# backplane-manual_selection.net
KiCad netlist of a schematic drawn in EAGLE
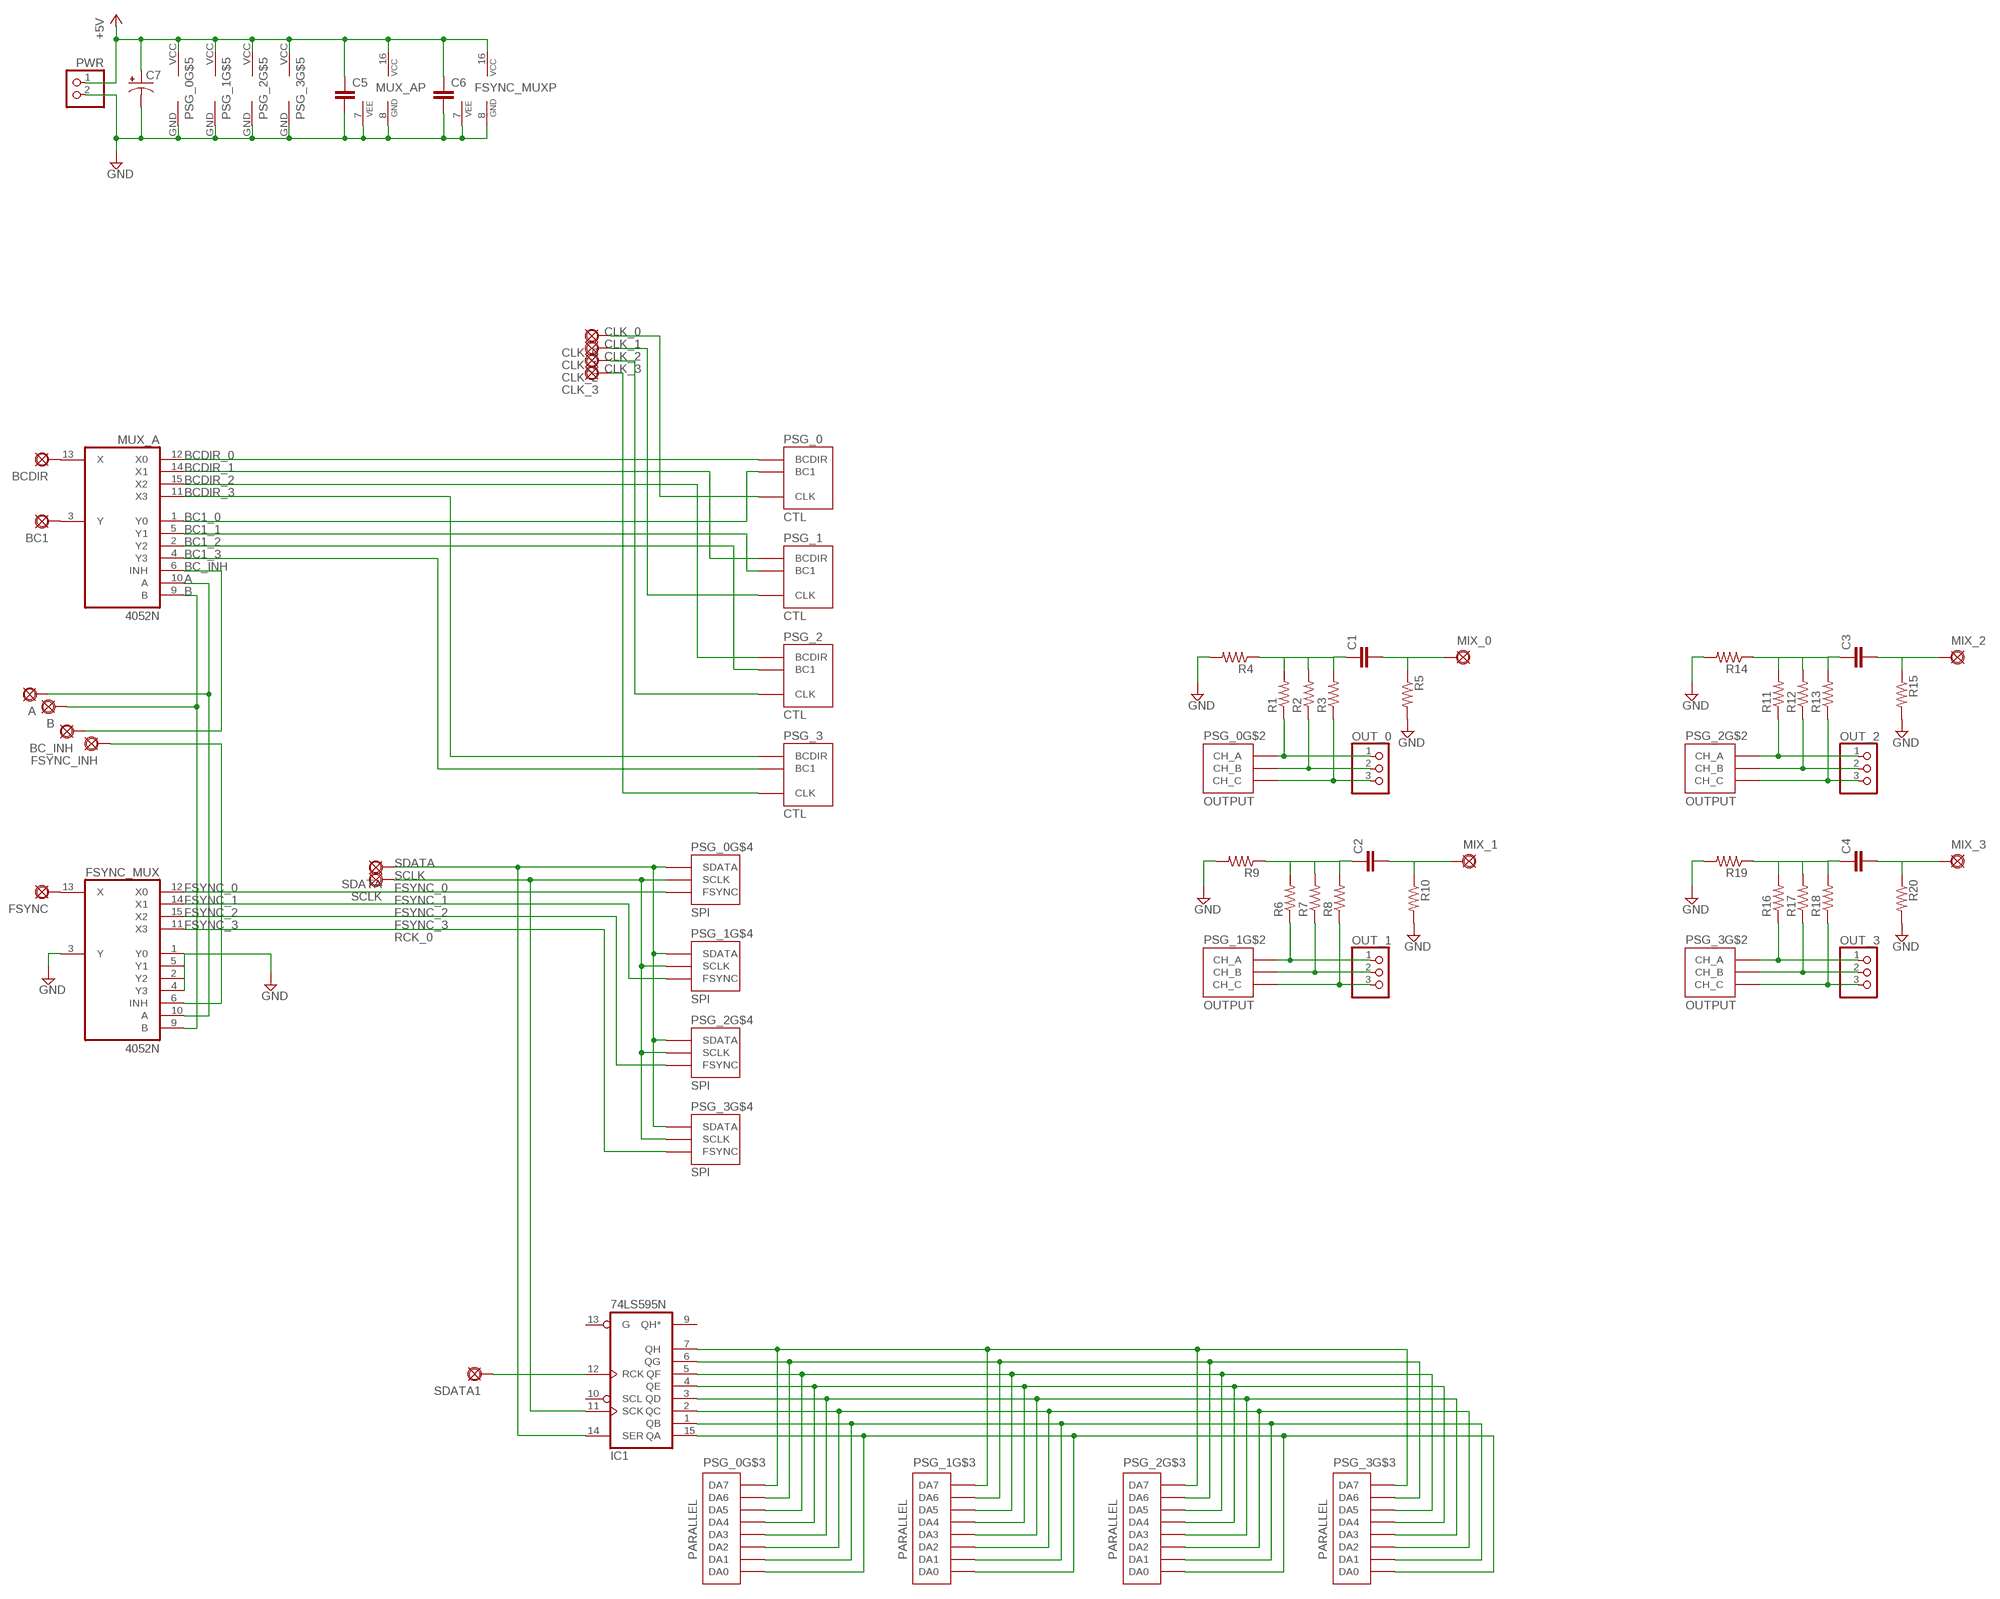
[diagram p0: schematic, sheet 1]

(export (version "E")
  (design (tool "Eeschema 10.0.6"))
  (components
    (comp (ref "A")
      (value "PAD")
      (footprint "eagle-import:SQUARE")
      (libsource (lib "eagle-import") (part "PAD"))
    )
    (comp (ref "B")
      (value "PAD")
      (footprint "eagle-import:SQUARE")
      (libsource (lib "eagle-import") (part "PAD"))
    )
    (comp (ref "BC1")
      (value "PAD")
      (footprint "eagle-import:SQUARE")
      (libsource (lib "eagle-import") (part "PAD"))
    )
    (comp (ref "BCDIR")
      (value "PAD")
      (footprint "eagle-import:SQUARE")
      (libsource (lib "eagle-import") (part "PAD"))
    )
    (comp (ref "BC_INH")
      (value "PAD")
      (footprint "eagle-import:SQUARE")
      (libsource (lib "eagle-import") (part "PAD"))
    )
    (comp (ref "C1")
      (value "080X0452")
      (footprint "eagle-import:080X045")
      (libsource (lib "eagle-import") (part "080X0452"))
    )
    (comp (ref "C2")
      (value "080X0452")
      (footprint "eagle-import:080X045")
      (libsource (lib "eagle-import") (part "080X0452"))
    )
    (comp (ref "C3")
      (value "080X0452")
      (footprint "eagle-import:080X045")
      (libsource (lib "eagle-import") (part "080X0452"))
    )
    (comp (ref "C4")
      (value "080X0452")
      (footprint "eagle-import:080X045")
      (libsource (lib "eagle-import") (part "080X0452"))
    )
    (comp (ref "C5")
      (value "050X030_0251")
      (footprint "eagle-import:050X030_025")
      (libsource (lib "eagle-import") (part "050X030_0251"))
    )
    (comp (ref "C6")
      (value "050X030_0251")
      (footprint "eagle-import:050X030_025")
      (libsource (lib "eagle-import") (part "050X030_0251"))
    )
    (comp (ref "C7")
      (value "0631")
      (footprint "eagle-import:063_025")
      (libsource (lib "eagle-import") (part "0631"))
    )
    (comp (ref "CLK_0")
      (value "PAD")
      (footprint "eagle-import:SQUARE")
      (libsource (lib "eagle-import") (part "PAD"))
    )
    (comp (ref "CLK_1")
      (value "PAD")
      (footprint "eagle-import:SQUARE")
      (libsource (lib "eagle-import") (part "PAD"))
    )
    (comp (ref "CLK_2")
      (value "PAD")
      (footprint "eagle-import:SQUARE")
      (libsource (lib "eagle-import") (part "PAD"))
    )
    (comp (ref "CLK_3")
      (value "PAD")
      (footprint "eagle-import:SQUARE")
      (libsource (lib "eagle-import") (part "PAD"))
    )
    (comp (ref "FSYNC")
      (value "PAD")
      (footprint "eagle-import:SQUARE")
      (libsource (lib "eagle-import") (part "PAD"))
    )
    (comp (ref "FSYNC_INH")
      (value "PAD")
      (footprint "eagle-import:SQUARE")
      (libsource (lib "eagle-import") (part "PAD"))
    )
    (comp (ref "FSYNC_MUX")
      (value "4052N")
      (footprint "eagle-import:DIL16")
      (libsource (lib "eagle-import") (part "4052N"))
    )
    (comp (ref "IC1")
      (value "74LS595N")
      (footprint "eagle-import:DIL16")
      (libsource (lib "eagle-import") (part "74595NLS"))
    )
    (comp (ref "MIX_0")
      (value "PAD")
      (footprint "eagle-import:SQUARE")
      (libsource (lib "eagle-import") (part "PAD"))
    )
    (comp (ref "MIX_1")
      (value "PAD")
      (footprint "eagle-import:SQUARE")
      (libsource (lib "eagle-import") (part "PAD"))
    )
    (comp (ref "MIX_2")
      (value "PAD")
      (footprint "eagle-import:SQUARE")
      (libsource (lib "eagle-import") (part "PAD"))
    )
    (comp (ref "MIX_3")
      (value "PAD")
      (footprint "eagle-import:SQUARE")
      (libsource (lib "eagle-import") (part "PAD"))
    )
    (comp (ref "MUX_A")
      (value "4052N")
      (footprint "eagle-import:DIL16")
      (libsource (lib "eagle-import") (part "4052N"))
    )
    (comp (ref "OUT_0")
      (value "PINHD-1X3")
      (footprint "eagle-import:1X03")
      (libsource (lib "eagle-import") (part "PINHD-1X3"))
    )
    (comp (ref "OUT_1")
      (value "PINHD-1X3")
      (footprint "eagle-import:1X03")
      (libsource (lib "eagle-import") (part "PINHD-1X3"))
    )
    (comp (ref "OUT_2")
      (value "PINHD-1X3")
      (footprint "eagle-import:1X03")
      (libsource (lib "eagle-import") (part "PINHD-1X3"))
    )
    (comp (ref "OUT_3")
      (value "PINHD-1X3")
      (footprint "eagle-import:1X03")
      (libsource (lib "eagle-import") (part "PINHD-1X3"))
    )
    (comp (ref "PSG_0")
      (value "PSG_DAUGHTER")
      (footprint "eagle-import:PSG_DAUGHTER")
      (libsource (lib "eagle-import") (part "PSG_DAUGHTER"))
    )
    (comp (ref "PSG_1")
      (value "PSG_DAUGHTER")
      (footprint "eagle-import:PSG_DAUGHTER")
      (libsource (lib "eagle-import") (part "PSG_DAUGHTER"))
    )
    (comp (ref "PSG_2")
      (value "PSG_DAUGHTER")
      (footprint "eagle-import:PSG_DAUGHTER")
      (libsource (lib "eagle-import") (part "PSG_DAUGHTER"))
    )
    (comp (ref "PSG_3")
      (value "PSG_DAUGHTER")
      (footprint "eagle-import:PSG_DAUGHTER")
      (libsource (lib "eagle-import") (part "PSG_DAUGHTER"))
    )
    (comp (ref "PWR")
      (value "PINHD-1X2")
      (footprint "eagle-import:1X02")
      (libsource (lib "eagle-import") (part "PINHD-1X2"))
    )
    (comp (ref "R1")
      (value "6MM.3")
      (footprint "eagle-import:R0207_3")
      (libsource (lib "eagle-import") (part "6MM.3"))
    )
    (comp (ref "R2")
      (value "6MM.3")
      (footprint "eagle-import:R0207_3")
      (libsource (lib "eagle-import") (part "6MM.3"))
    )
    (comp (ref "R3")
      (value "6MM.3")
      (footprint "eagle-import:R0207_3")
      (libsource (lib "eagle-import") (part "6MM.3"))
    )
    (comp (ref "R4")
      (value "6MM.3")
      (footprint "eagle-import:R0207_3")
      (libsource (lib "eagle-import") (part "6MM.3"))
    )
    (comp (ref "R5")
      (value "6MM.3")
      (footprint "eagle-import:R0207_3")
      (libsource (lib "eagle-import") (part "6MM.3"))
    )
    (comp (ref "R6")
      (value "6MM.3")
      (footprint "eagle-import:R0207_3")
      (libsource (lib "eagle-import") (part "6MM.3"))
    )
    (comp (ref "R7")
      (value "6MM.3")
      (footprint "eagle-import:R0207_3")
      (libsource (lib "eagle-import") (part "6MM.3"))
    )
    (comp (ref "R8")
      (value "6MM.3")
      (footprint "eagle-import:R0207_3")
      (libsource (lib "eagle-import") (part "6MM.3"))
    )
    (comp (ref "R9")
      (value "6MM.3")
      (footprint "eagle-import:R0207_3")
      (libsource (lib "eagle-import") (part "6MM.3"))
    )
    (comp (ref "R10")
      (value "6MM.3")
      (footprint "eagle-import:R0207_3")
      (libsource (lib "eagle-import") (part "6MM.3"))
    )
    (comp (ref "R11")
      (value "6MM.3")
      (footprint "eagle-import:R0207_3")
      (libsource (lib "eagle-import") (part "6MM.3"))
    )
    (comp (ref "R12")
      (value "6MM.3")
      (footprint "eagle-import:R0207_3")
      (libsource (lib "eagle-import") (part "6MM.3"))
    )
    (comp (ref "R13")
      (value "6MM.3")
      (footprint "eagle-import:R0207_3")
      (libsource (lib "eagle-import") (part "6MM.3"))
    )
    (comp (ref "R14")
      (value "6MM.3")
      (footprint "eagle-import:R0207_3")
      (libsource (lib "eagle-import") (part "6MM.3"))
    )
    (comp (ref "R15")
      (value "6MM.3")
      (footprint "eagle-import:R0207_3")
      (libsource (lib "eagle-import") (part "6MM.3"))
    )
    (comp (ref "R16")
      (value "6MM.3")
      (footprint "eagle-import:R0207_3")
      (libsource (lib "eagle-import") (part "6MM.3"))
    )
    (comp (ref "R17")
      (value "6MM.3")
      (footprint "eagle-import:R0207_3")
      (libsource (lib "eagle-import") (part "6MM.3"))
    )
    (comp (ref "R18")
      (value "6MM.3")
      (footprint "eagle-import:R0207_3")
      (libsource (lib "eagle-import") (part "6MM.3"))
    )
    (comp (ref "R19")
      (value "6MM.3")
      (footprint "eagle-import:R0207_3")
      (libsource (lib "eagle-import") (part "6MM.3"))
    )
    (comp (ref "R20")
      (value "6MM.3")
      (footprint "eagle-import:R0207_3")
      (libsource (lib "eagle-import") (part "6MM.3"))
    )
    (comp (ref "SCLK")
      (value "PAD")
      (footprint "eagle-import:SQUARE")
      (libsource (lib "eagle-import") (part "PAD"))
    )
    (comp (ref "SDATA")
      (value "PAD")
      (footprint "eagle-import:SQUARE")
      (libsource (lib "eagle-import") (part "PAD"))
    )
    (comp (ref "SDATA1")
      (value "PAD")
      (footprint "eagle-import:SQUARE")
      (libsource (lib "eagle-import") (part "PAD"))
    )
  )
  (nets
    (net (code "1") (name "+5V") (class "Default")
      (node (ref "C5") (pin "1") (pinfunction "1_1") (pintype "passive"))
      (node (ref "C6") (pin "1") (pinfunction "1_1") (pintype "passive"))
      (node (ref "C7") (pin "+") (pinfunction "+_+") (pintype "passive"))
      (node (ref "FSYNC_MUX") (pin "16") (pinfunction "VCC_16") (pintype "power_in"))
      (node (ref "MUX_A") (pin "16") (pinfunction "VCC_16") (pintype "power_in"))
      (node (ref "PSG_0") (pin "VCC") (pinfunction "VCC_VCC") (pintype "power_in"))
      (node (ref "PSG_1") (pin "VCC") (pinfunction "VCC_VCC") (pintype "power_in"))
      (node (ref "PSG_2") (pin "VCC") (pinfunction "VCC_VCC") (pintype "power_in"))
      (node (ref "PSG_3") (pin "VCC") (pinfunction "VCC_VCC") (pintype "power_in"))
      (node (ref "PWR") (pin "1") (pinfunction "1_1") (pintype "passive"))
    )
    (net (code "2") (name "/A") (class "Default")
      (node (ref "A") (pin "1") (pinfunction "PAD_1") (pintype "passive"))
      (node (ref "FSYNC_MUX") (pin "10") (pinfunction "A_10") (pintype "input"))
      (node (ref "MUX_A") (pin "10") (pinfunction "A_10") (pintype "input"))
    )
    (net (code "3") (name "/B") (class "Default")
      (node (ref "B") (pin "1") (pinfunction "PAD_1") (pintype "passive"))
      (node (ref "FSYNC_MUX") (pin "9") (pinfunction "B_9") (pintype "input"))
      (node (ref "MUX_A") (pin "9") (pinfunction "B_9") (pintype "input"))
    )
    (net (code "4") (name "/BC1_0") (class "Default")
      (node (ref "MUX_A") (pin "1") (pinfunction "Y0_1") (pintype "bidirectional"))
      (node (ref "PSG_0") (pin "BC1") (pinfunction "BC1_BC1") (pintype "input"))
    )
    (net (code "5") (name "/BC1_1") (class "Default")
      (node (ref "MUX_A") (pin "5") (pinfunction "Y1_5") (pintype "bidirectional"))
      (node (ref "PSG_1") (pin "BC1") (pinfunction "BC1_BC1") (pintype "input"))
    )
    (net (code "6") (name "/BC1_2") (class "Default")
      (node (ref "MUX_A") (pin "2") (pinfunction "Y2_2") (pintype "bidirectional"))
      (node (ref "PSG_2") (pin "BC1") (pinfunction "BC1_BC1") (pintype "input"))
    )
    (net (code "7") (name "/BC1_3") (class "Default")
      (node (ref "MUX_A") (pin "4") (pinfunction "Y3_4") (pintype "bidirectional"))
      (node (ref "PSG_3") (pin "BC1") (pinfunction "BC1_BC1") (pintype "input"))
    )
    (net (code "8") (name "/BCDIR_0") (class "Default")
      (node (ref "MUX_A") (pin "12") (pinfunction "X0_12") (pintype "bidirectional"))
      (node (ref "PSG_0") (pin "BCDIR") (pinfunction "BCDIR_BCDIR") (pintype "input"))
    )
    (net (code "9") (name "/BCDIR_1") (class "Default")
      (node (ref "MUX_A") (pin "14") (pinfunction "X1_14") (pintype "bidirectional"))
      (node (ref "PSG_1") (pin "BCDIR") (pinfunction "BCDIR_BCDIR") (pintype "input"))
    )
    (net (code "10") (name "/BCDIR_2") (class "Default")
      (node (ref "MUX_A") (pin "15") (pinfunction "X2_15") (pintype "bidirectional"))
      (node (ref "PSG_2") (pin "BCDIR") (pinfunction "BCDIR_BCDIR") (pintype "input"))
    )
    (net (code "11") (name "/BCDIR_3") (class "Default")
      (node (ref "MUX_A") (pin "11") (pinfunction "X3_11") (pintype "bidirectional"))
      (node (ref "PSG_3") (pin "BCDIR") (pinfunction "BCDIR_BCDIR") (pintype "input"))
    )
    (net (code "12") (name "/BC_INH") (class "Default")
      (node (ref "BC_INH") (pin "1") (pinfunction "PAD_1") (pintype "passive"))
      (node (ref "MUX_A") (pin "6") (pinfunction "INH_6") (pintype "input"))
    )
    (net (code "13") (name "/CLK_0") (class "Default")
      (node (ref "CLK_0") (pin "1") (pinfunction "PAD_1") (pintype "passive"))
      (node (ref "PSG_0") (pin "CLK") (pinfunction "CLK_CLK") (pintype "input"))
    )
    (net (code "14") (name "/CLK_1") (class "Default")
      (node (ref "CLK_1") (pin "1") (pinfunction "PAD_1") (pintype "passive"))
      (node (ref "PSG_1") (pin "CLK") (pinfunction "CLK_CLK") (pintype "input"))
    )
    (net (code "15") (name "/CLK_2") (class "Default")
      (node (ref "CLK_2") (pin "1") (pinfunction "PAD_1") (pintype "passive"))
      (node (ref "PSG_2") (pin "CLK") (pinfunction "CLK_CLK") (pintype "input"))
    )
    (net (code "16") (name "/CLK_3") (class "Default")
      (node (ref "CLK_3") (pin "1") (pinfunction "PAD_1") (pintype "passive"))
      (node (ref "PSG_3") (pin "CLK") (pinfunction "CLK_CLK") (pintype "input"))
    )
    (net (code "17") (name "/FSYNC_0") (class "Default")
      (node (ref "FSYNC_MUX") (pin "12") (pinfunction "X0_12") (pintype "bidirectional"))
      (node (ref "PSG_0") (pin "FSYNC") (pinfunction "FSYNC_FSYNC") (pintype "input"))
    )
    (net (code "18") (name "/FSYNC_1") (class "Default")
      (node (ref "FSYNC_MUX") (pin "14") (pinfunction "X1_14") (pintype "bidirectional"))
      (node (ref "PSG_1") (pin "FSYNC") (pinfunction "FSYNC_FSYNC") (pintype "input"))
    )
    (net (code "19") (name "/FSYNC_2") (class "Default")
      (node (ref "FSYNC_MUX") (pin "15") (pinfunction "X2_15") (pintype "bidirectional"))
      (node (ref "PSG_2") (pin "FSYNC") (pinfunction "FSYNC_FSYNC") (pintype "input"))
    )
    (net (code "20") (name "/FSYNC_3") (class "Default")
      (node (ref "FSYNC_MUX") (pin "11") (pinfunction "X3_11") (pintype "bidirectional"))
      (node (ref "PSG_3") (pin "FSYNC") (pinfunction "FSYNC_FSYNC") (pintype "input"))
    )
    (net (code "21") (name "/RCK_0") (class "Default")
      (node (ref "IC1") (pin "12") (pinfunction "RCK_12") (pintype "input"))
      (node (ref "SDATA1") (pin "1") (pinfunction "PAD_1") (pintype "passive"))
    )
    (net (code "22") (name "/SCLK") (class "Default")
      (node (ref "IC1") (pin "11") (pinfunction "SCK_11") (pintype "input"))
      (node (ref "PSG_0") (pin "SCLK") (pinfunction "SCLK_SCLK") (pintype "input"))
      (node (ref "PSG_1") (pin "SCLK") (pinfunction "SCLK_SCLK") (pintype "input"))
      (node (ref "PSG_2") (pin "SCLK") (pinfunction "SCLK_SCLK") (pintype "input"))
      (node (ref "PSG_3") (pin "SCLK") (pinfunction "SCLK_SCLK") (pintype "input"))
      (node (ref "SCLK") (pin "1") (pinfunction "PAD_1") (pintype "passive"))
    )
    (net (code "23") (name "/SDATA") (class "Default")
      (node (ref "IC1") (pin "14") (pinfunction "SER_14") (pintype "input"))
      (node (ref "PSG_0") (pin "SDATA") (pinfunction "SDATA_SDATA") (pintype "bidirectional"))
      (node (ref "PSG_1") (pin "SDATA") (pinfunction "SDATA_SDATA") (pintype "bidirectional"))
      (node (ref "PSG_2") (pin "SDATA") (pinfunction "SDATA_SDATA") (pintype "bidirectional"))
      (node (ref "PSG_3") (pin "SDATA") (pinfunction "SDATA_SDATA") (pintype "bidirectional"))
      (node (ref "SDATA") (pin "1") (pinfunction "PAD_1") (pintype "passive"))
    )
    (net (code "24") (name "GND") (class "Default")
      (node (ref "C5") (pin "2") (pinfunction "2_2") (pintype "passive"))
      (node (ref "C6") (pin "2") (pinfunction "2_2") (pintype "passive"))
      (node (ref "C7") (pin "-") (pinfunction "-_-") (pintype "passive"))
      (node (ref "FSYNC_MUX") (pin "1") (pinfunction "Y0_1") (pintype "bidirectional"))
      (node (ref "FSYNC_MUX") (pin "2") (pinfunction "Y2_2") (pintype "bidirectional"))
      (node (ref "FSYNC_MUX") (pin "3") (pinfunction "Y_3") (pintype "bidirectional"))
      (node (ref "FSYNC_MUX") (pin "4") (pinfunction "Y3_4") (pintype "bidirectional"))
      (node (ref "FSYNC_MUX") (pin "5") (pinfunction "Y1_5") (pintype "bidirectional"))
      (node (ref "FSYNC_MUX") (pin "7") (pinfunction "VEE_7") (pintype "power_in"))
      (node (ref "FSYNC_MUX") (pin "8") (pinfunction "GND_8") (pintype "power_in"))
      (node (ref "MUX_A") (pin "7") (pinfunction "VEE_7") (pintype "power_in"))
      (node (ref "MUX_A") (pin "8") (pinfunction "GND_8") (pintype "power_in"))
      (node (ref "PSG_0") (pin "GND") (pinfunction "GND_GND") (pintype "power_in"))
      (node (ref "PSG_1") (pin "GND") (pinfunction "GND_GND") (pintype "power_in"))
      (node (ref "PSG_2") (pin "GND") (pinfunction "GND_GND") (pintype "power_in"))
      (node (ref "PSG_3") (pin "GND") (pinfunction "GND_GND") (pintype "power_in"))
      (node (ref "PWR") (pin "2") (pinfunction "2_2") (pintype "passive"))
      (node (ref "R10") (pin "2") (pinfunction "2_2") (pintype "passive"))
      (node (ref "R14") (pin "2") (pinfunction "2_2") (pintype "passive"))
      (node (ref "R15") (pin "2") (pinfunction "2_2") (pintype "passive"))
      (node (ref "R19") (pin "2") (pinfunction "2_2") (pintype "passive"))
      (node (ref "R20") (pin "2") (pinfunction "2_2") (pintype "passive"))
      (node (ref "R4") (pin "2") (pinfunction "2_2") (pintype "passive"))
      (node (ref "R5") (pin "2") (pinfunction "2_2") (pintype "passive"))
      (node (ref "R9") (pin "2") (pinfunction "2_2") (pintype "passive"))
    )
    (net (code "25") (name "Net-(BC1-PAD)") (class "Default")
      (node (ref "BC1") (pin "1") (pinfunction "PAD_1") (pintype "passive"))
      (node (ref "MUX_A") (pin "3") (pinfunction "Y_3") (pintype "bidirectional"))
    )
    (net (code "26") (name "Net-(BCDIR-PAD)") (class "Default")
      (node (ref "BCDIR") (pin "1") (pinfunction "PAD_1") (pintype "passive"))
      (node (ref "MUX_A") (pin "13") (pinfunction "X_13") (pintype "bidirectional"))
    )
    (net (code "27") (name "Net-(C1-Pad1)") (class "Default")
      (node (ref "C1") (pin "1") (pinfunction "1_1") (pintype "passive"))
      (node (ref "R1") (pin "2") (pinfunction "2_2") (pintype "passive"))
      (node (ref "R2") (pin "2") (pinfunction "2_2") (pintype "passive"))
      (node (ref "R3") (pin "2") (pinfunction "2_2") (pintype "passive"))
      (node (ref "R4") (pin "1") (pinfunction "1_1") (pintype "passive"))
    )
    (net (code "28") (name "Net-(C2-Pad1)") (class "Default")
      (node (ref "C2") (pin "1") (pinfunction "1_1") (pintype "passive"))
      (node (ref "R6") (pin "2") (pinfunction "2_2") (pintype "passive"))
      (node (ref "R7") (pin "2") (pinfunction "2_2") (pintype "passive"))
      (node (ref "R8") (pin "2") (pinfunction "2_2") (pintype "passive"))
      (node (ref "R9") (pin "1") (pinfunction "1_1") (pintype "passive"))
    )
    (net (code "29") (name "Net-(C3-Pad1)") (class "Default")
      (node (ref "C3") (pin "1") (pinfunction "1_1") (pintype "passive"))
      (node (ref "R11") (pin "2") (pinfunction "2_2") (pintype "passive"))
      (node (ref "R12") (pin "2") (pinfunction "2_2") (pintype "passive"))
      (node (ref "R13") (pin "2") (pinfunction "2_2") (pintype "passive"))
      (node (ref "R14") (pin "1") (pinfunction "1_1") (pintype "passive"))
    )
    (net (code "30") (name "Net-(C4-Pad1)") (class "Default")
      (node (ref "C4") (pin "1") (pinfunction "1_1") (pintype "passive"))
      (node (ref "R16") (pin "2") (pinfunction "2_2") (pintype "passive"))
      (node (ref "R17") (pin "2") (pinfunction "2_2") (pintype "passive"))
      (node (ref "R18") (pin "2") (pinfunction "2_2") (pintype "passive"))
      (node (ref "R19") (pin "1") (pinfunction "1_1") (pintype "passive"))
    )
    (net (code "31") (name "Net-(FSYNC-PAD)") (class "Default")
      (node (ref "FSYNC") (pin "1") (pinfunction "PAD_1") (pintype "passive"))
      (node (ref "FSYNC_MUX") (pin "13") (pinfunction "X_13") (pintype "bidirectional"))
    )
    (net (code "32") (name "Net-(FSYNC_INH-PAD)") (class "Default")
      (node (ref "FSYNC_INH") (pin "1") (pinfunction "PAD_1") (pintype "passive"))
      (node (ref "FSYNC_MUX") (pin "6") (pinfunction "INH_6") (pintype "input"))
    )
    (net (code "33") (name "Net-(IC1A-QA)") (class "Default")
      (node (ref "IC1") (pin "15") (pinfunction "QA_15") (pintype "tri_state"))
      (node (ref "PSG_0") (pin "DA0") (pinfunction "DA0_DA0") (pintype "bidirectional"))
      (node (ref "PSG_1") (pin "DA0") (pinfunction "DA0_DA0") (pintype "bidirectional"))
      (node (ref "PSG_2") (pin "DA0") (pinfunction "DA0_DA0") (pintype "bidirectional"))
      (node (ref "PSG_3") (pin "DA0") (pinfunction "DA0_DA0") (pintype "bidirectional"))
    )
    (net (code "34") (name "Net-(IC1A-QB)") (class "Default")
      (node (ref "IC1") (pin "1") (pinfunction "QB_1") (pintype "tri_state"))
      (node (ref "PSG_0") (pin "DA1") (pinfunction "DA1_DA1") (pintype "bidirectional"))
      (node (ref "PSG_1") (pin "DA1") (pinfunction "DA1_DA1") (pintype "bidirectional"))
      (node (ref "PSG_2") (pin "DA1") (pinfunction "DA1_DA1") (pintype "bidirectional"))
      (node (ref "PSG_3") (pin "DA1") (pinfunction "DA1_DA1") (pintype "bidirectional"))
    )
    (net (code "35") (name "Net-(IC1A-QC)") (class "Default")
      (node (ref "IC1") (pin "2") (pinfunction "QC_2") (pintype "tri_state"))
      (node (ref "PSG_0") (pin "DA2") (pinfunction "DA2_DA2") (pintype "bidirectional"))
      (node (ref "PSG_1") (pin "DA2") (pinfunction "DA2_DA2") (pintype "bidirectional"))
      (node (ref "PSG_2") (pin "DA2") (pinfunction "DA2_DA2") (pintype "bidirectional"))
      (node (ref "PSG_3") (pin "DA2") (pinfunction "DA2_DA2") (pintype "bidirectional"))
    )
    (net (code "36") (name "Net-(IC1A-QD)") (class "Default")
      (node (ref "IC1") (pin "3") (pinfunction "QD_3") (pintype "tri_state"))
      (node (ref "PSG_0") (pin "DA3") (pinfunction "DA3_DA3") (pintype "bidirectional"))
      (node (ref "PSG_1") (pin "DA3") (pinfunction "DA3_DA3") (pintype "bidirectional"))
      (node (ref "PSG_2") (pin "DA3") (pinfunction "DA3_DA3") (pintype "bidirectional"))
      (node (ref "PSG_3") (pin "DA3") (pinfunction "DA3_DA3") (pintype "bidirectional"))
    )
    (net (code "37") (name "Net-(IC1A-QE)") (class "Default")
      (node (ref "IC1") (pin "4") (pinfunction "QE_4") (pintype "tri_state"))
      (node (ref "PSG_0") (pin "DA4") (pinfunction "DA4_DA4") (pintype "bidirectional"))
      (node (ref "PSG_1") (pin "DA4") (pinfunction "DA4_DA4") (pintype "bidirectional"))
      (node (ref "PSG_2") (pin "DA4") (pinfunction "DA4_DA4") (pintype "bidirectional"))
      (node (ref "PSG_3") (pin "DA4") (pinfunction "DA4_DA4") (pintype "bidirectional"))
    )
    (net (code "38") (name "Net-(IC1A-QF)") (class "Default")
      (node (ref "IC1") (pin "5") (pinfunction "QF_5") (pintype "tri_state"))
      (node (ref "PSG_0") (pin "DA5") (pinfunction "DA5_DA5") (pintype "bidirectional"))
      (node (ref "PSG_1") (pin "DA5") (pinfunction "DA5_DA5") (pintype "bidirectional"))
      (node (ref "PSG_2") (pin "DA5") (pinfunction "DA5_DA5") (pintype "bidirectional"))
      (node (ref "PSG_3") (pin "DA5") (pinfunction "DA5_DA5") (pintype "bidirectional"))
    )
    (net (code "39") (name "Net-(IC1A-QG)") (class "Default")
      (node (ref "IC1") (pin "6") (pinfunction "QG_6") (pintype "tri_state"))
      (node (ref "PSG_0") (pin "DA6") (pinfunction "DA6_DA6") (pintype "bidirectional"))
      (node (ref "PSG_1") (pin "DA6") (pinfunction "DA6_DA6") (pintype "bidirectional"))
      (node (ref "PSG_2") (pin "DA6") (pinfunction "DA6_DA6") (pintype "bidirectional"))
      (node (ref "PSG_3") (pin "DA6") (pinfunction "DA6_DA6") (pintype "bidirectional"))
    )
    (net (code "40") (name "Net-(IC1A-QH)") (class "Default")
      (node (ref "IC1") (pin "7") (pinfunction "QH_7") (pintype "tri_state"))
      (node (ref "PSG_0") (pin "DA7") (pinfunction "DA7_DA7") (pintype "bidirectional"))
      (node (ref "PSG_1") (pin "DA7") (pinfunction "DA7_DA7") (pintype "bidirectional"))
      (node (ref "PSG_2") (pin "DA7") (pinfunction "DA7_DA7") (pintype "bidirectional"))
      (node (ref "PSG_3") (pin "DA7") (pinfunction "DA7_DA7") (pintype "bidirectional"))
    )
    (net (code "41") (name "Net-(MIX_0-PAD)") (class "Default")
      (node (ref "C1") (pin "2") (pinfunction "2_2") (pintype "passive"))
      (node (ref "MIX_0") (pin "1") (pinfunction "PAD_1") (pintype "passive"))
      (node (ref "R5") (pin "1") (pinfunction "1_1") (pintype "passive"))
    )
    (net (code "42") (name "Net-(MIX_1-PAD)") (class "Default")
      (node (ref "C2") (pin "2") (pinfunction "2_2") (pintype "passive"))
      (node (ref "MIX_1") (pin "1") (pinfunction "PAD_1") (pintype "passive"))
      (node (ref "R10") (pin "1") (pinfunction "1_1") (pintype "passive"))
    )
    (net (code "43") (name "Net-(MIX_2-PAD)") (class "Default")
      (node (ref "C3") (pin "2") (pinfunction "2_2") (pintype "passive"))
      (node (ref "MIX_2") (pin "1") (pinfunction "PAD_1") (pintype "passive"))
      (node (ref "R15") (pin "1") (pinfunction "1_1") (pintype "passive"))
    )
    (net (code "44") (name "Net-(MIX_3-PAD)") (class "Default")
      (node (ref "C4") (pin "2") (pinfunction "2_2") (pintype "passive"))
      (node (ref "MIX_3") (pin "1") (pinfunction "PAD_1") (pintype "passive"))
      (node (ref "R20") (pin "1") (pinfunction "1_1") (pintype "passive"))
    )
    (net (code "45") (name "Net-(PSG_0B-CH_A)") (class "Default")
      (node (ref "OUT_0") (pin "1") (pinfunction "1_1") (pintype "passive"))
      (node (ref "PSG_0") (pin "OUT_A") (pinfunction "CH_A_OUT_A") (pintype "input"))
      (node (ref "R1") (pin "1") (pinfunction "1_1") (pintype "passive"))
    )
    (net (code "46") (name "Net-(PSG_0B-CH_B)") (class "Default")
      (node (ref "OUT_0") (pin "2") (pinfunction "2_2") (pintype "passive"))
      (node (ref "PSG_0") (pin "OUT_B") (pinfunction "CH_B_OUT_B") (pintype "input"))
      (node (ref "R2") (pin "1") (pinfunction "1_1") (pintype "passive"))
    )
    (net (code "47") (name "Net-(PSG_0B-CH_C)") (class "Default")
      (node (ref "OUT_0") (pin "3") (pinfunction "3_3") (pintype "passive"))
      (node (ref "PSG_0") (pin "OUT_C") (pinfunction "CH_C_OUT_C") (pintype "input"))
      (node (ref "R3") (pin "1") (pinfunction "1_1") (pintype "passive"))
    )
    (net (code "48") (name "Net-(PSG_1B-CH_A)") (class "Default")
      (node (ref "OUT_1") (pin "1") (pinfunction "1_1") (pintype "passive"))
      (node (ref "PSG_1") (pin "OUT_A") (pinfunction "CH_A_OUT_A") (pintype "input"))
      (node (ref "R6") (pin "1") (pinfunction "1_1") (pintype "passive"))
    )
    (net (code "49") (name "Net-(PSG_1B-CH_B)") (class "Default")
      (node (ref "OUT_1") (pin "2") (pinfunction "2_2") (pintype "passive"))
      (node (ref "PSG_1") (pin "OUT_B") (pinfunction "CH_B_OUT_B") (pintype "input"))
      (node (ref "R7") (pin "1") (pinfunction "1_1") (pintype "passive"))
    )
    (net (code "50") (name "Net-(PSG_1B-CH_C)") (class "Default")
      (node (ref "OUT_1") (pin "3") (pinfunction "3_3") (pintype "passive"))
      (node (ref "PSG_1") (pin "OUT_C") (pinfunction "CH_C_OUT_C") (pintype "input"))
      (node (ref "R8") (pin "1") (pinfunction "1_1") (pintype "passive"))
    )
    (net (code "51") (name "Net-(PSG_2B-CH_A)") (class "Default")
      (node (ref "OUT_2") (pin "1") (pinfunction "1_1") (pintype "passive"))
      (node (ref "PSG_2") (pin "OUT_A") (pinfunction "CH_A_OUT_A") (pintype "input"))
      (node (ref "R11") (pin "1") (pinfunction "1_1") (pintype "passive"))
    )
    (net (code "52") (name "Net-(PSG_2B-CH_B)") (class "Default")
      (node (ref "OUT_2") (pin "2") (pinfunction "2_2") (pintype "passive"))
      (node (ref "PSG_2") (pin "OUT_B") (pinfunction "CH_B_OUT_B") (pintype "input"))
      (node (ref "R12") (pin "1") (pinfunction "1_1") (pintype "passive"))
    )
    (net (code "53") (name "Net-(PSG_2B-CH_C)") (class "Default")
      (node (ref "OUT_2") (pin "3") (pinfunction "3_3") (pintype "passive"))
      (node (ref "PSG_2") (pin "OUT_C") (pinfunction "CH_C_OUT_C") (pintype "input"))
      (node (ref "R13") (pin "1") (pinfunction "1_1") (pintype "passive"))
    )
    (net (code "54") (name "Net-(PSG_3B-CH_A)") (class "Default")
      (node (ref "OUT_3") (pin "1") (pinfunction "1_1") (pintype "passive"))
      (node (ref "PSG_3") (pin "OUT_A") (pinfunction "CH_A_OUT_A") (pintype "input"))
      (node (ref "R16") (pin "1") (pinfunction "1_1") (pintype "passive"))
    )
    (net (code "55") (name "Net-(PSG_3B-CH_B)") (class "Default")
      (node (ref "OUT_3") (pin "2") (pinfunction "2_2") (pintype "passive"))
      (node (ref "PSG_3") (pin "OUT_B") (pinfunction "CH_B_OUT_B") (pintype "input"))
      (node (ref "R17") (pin "1") (pinfunction "1_1") (pintype "passive"))
    )
    (net (code "56") (name "Net-(PSG_3B-CH_C)") (class "Default")
      (node (ref "OUT_3") (pin "3") (pinfunction "3_3") (pintype "passive"))
      (node (ref "PSG_3") (pin "OUT_C") (pinfunction "CH_C_OUT_C") (pintype "input"))
      (node (ref "R18") (pin "1") (pinfunction "1_1") (pintype "passive"))
    )
    (net (code "57") (name "unconnected-(IC1A-G-Pad13)") (class "Default")
      (node (ref "IC1") (pin "13") (pinfunction "G_13") (pintype "input"))
    )
    (net (code "58") (name "unconnected-(IC1A-QH*-Pad9)") (class "Default")
      (node (ref "IC1") (pin "9") (pinfunction "QH*_9") (pintype "tri_state"))
    )
    (net (code "59") (name "unconnected-(IC1A-SCL-Pad10)") (class "Default")
      (node (ref "IC1") (pin "10") (pinfunction "SCL_10") (pintype "input"))
    )
  )
)
